# sprinkler_photon_0v2.net
KiCad netlist of a schematic drawn in Altium Designer
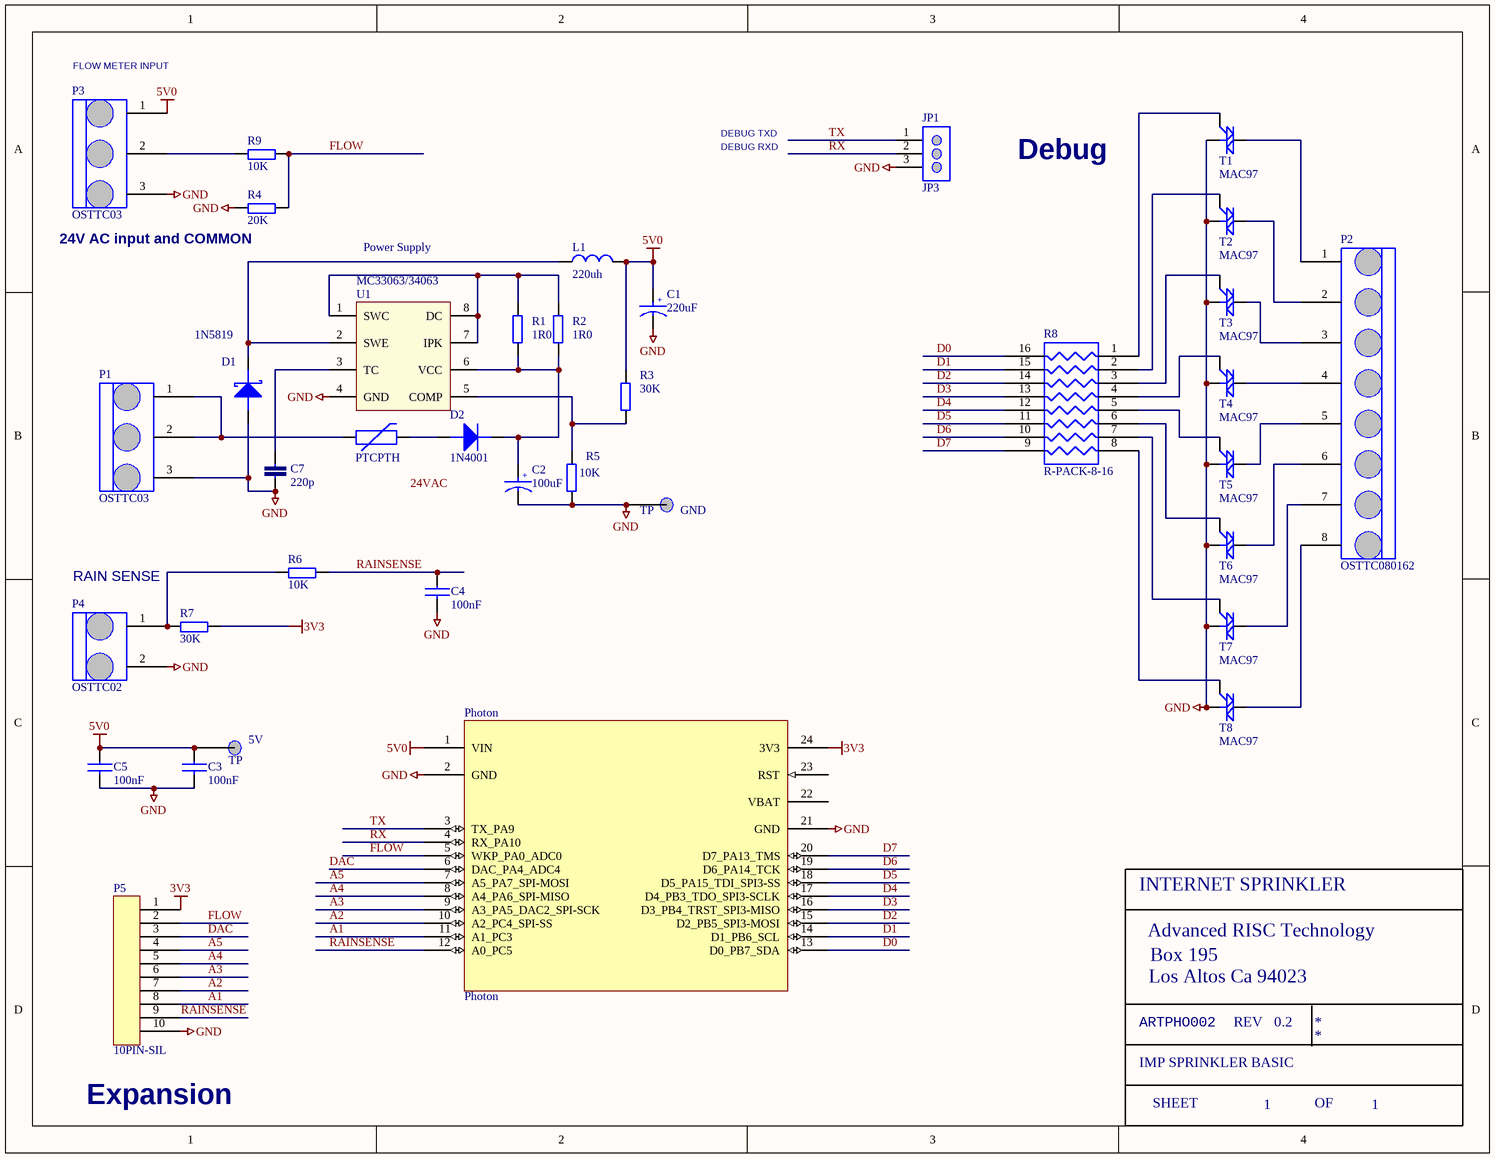
[diagram p0: sprinkler_photon_0v2.SchDoc]

(export (version "E")
  (design (tool "Eeschema 10.0.6"))
  (components
    (comp (ref "5V")
      (value "TP")
      (footprint "SIP-1")
      (description "Test Point")
      (libsource (lib "visible_energy") (part "TPS"))
    )
    (comp (ref "C1")
      (value "220uF")
      (footprint "RB-2MM-5MM")
      (description "CAP ALUM 220UF 6.3V 20% RADIAL")
      (fields (field (name "DISTRIBUTOR PART#") "493-1004-ND") (field (name "MANUFACTURER") "Nichicon"))
      (libsource (lib "visible_energy") (part "CAP POL"))
    )
    (comp (ref "C2")
      (value "100uF")
      (footprint "RB-3.5MM-8MM")
      (description "CAP ALUM 100UF 50V 20% RADIAL")
      (fields (field (name "DISTRIBUTOR PART#") "493-1107-ND") (field (name "MANUFACTURER") "Nichicon"))
      (libsource (lib "visible_energy") (part "CAP POL"))
    )
    (comp (ref "C3")
      (value "100nF")
      (footprint "RAD-0.1")
      (description "CAP CER 0.1UF 25V 10% RADIAL")
      (fields (field (name "DISTRIBUTOR PART#") "445-8421-ND") (field (name "MANUFACTURER") "TDK"))
      (libsource (lib "visible_energy") (part "CAP NP"))
    )
    (comp (ref "C4")
      (value "100nF")
      (footprint "RAD-0.1")
      (description "CAP CER 0.1UF 25V 10% RADIAL")
      (fields (field (name "DISTRIBUTOR PART#") "445-8421-ND") (field (name "MANUFACTURER") "TDK"))
      (libsource (lib "visible_energy") (part "CAP NP"))
    )
    (comp (ref "C5")
      (value "100nF")
      (footprint "RAD-0.1")
      (description "CAP CER 0.1UF 25V 10% RADIAL")
      (fields (field (name "DISTRIBUTOR PART#") "445-8421-ND") (field (name "MANUFACTURER") "TDK"))
      (libsource (lib "visible_energy") (part "CAP NP"))
    )
    (comp (ref "C7")
      (value "220p")
      (footprint "thruholepcb:RADCAP-0.1")
      (description "CAP CER 220PF 100V 5% RADIAL")
      (fields (field (name "DISTRIBUTOR PART#") "478-4847-ND") (field (name "MANUFACTURER") "AVX"))
      (libsource (lib "rcl") (part "C-EU025-024X044"))
    )
    (comp (ref "D1")
      (value "1N5819")
      (footprint "AXIAL-0.4 - DIODE")
      (description "DIODE SCHOTTKY 40V 1A DO-41")
      (fields (field (name "MANUFACTURER") "Diodes") (field (name "MANUFACTURER PART#") "1N5819-T"))
      (libsource (lib "visible_energy") (part "DIODE SCHOTTKY"))
    )
    (comp (ref "D2")
      (value "1N4001")
      (footprint "AXIAL-0.4 - DIODE")
      (description "RECTIFIER 50V 1A DO-41")
      (fields (field (name "MANUFACTURER") "Diodes") (field (name "MANUFACTURER PART#") "1N4001-T"))
      (libsource (lib "visible_energy") (part "DIODE"))
    )
    (comp (ref "GND")
      (value "TP")
      (footprint "SIP-1")
      (description "Test Point")
      (libsource (lib "visible_energy") (part "TPS"))
    )
    (comp (ref "JP1")
      (value "JP3")
      (footprint "SIP-3")
      (description "3 PIN JUMPER")
      (fields (field (name "MANUFACTURER") "Harwin") (field (name "DISTRIBUTOR PART#") "952-2264-ND"))
      (libsource (lib "connector") (part "JP3"))
    )
    (comp (ref "L1")
      (value "220uh")
      (footprint "thruholepcb:RB-5MM - 9MMDIA")
      (description "Inductor")
      (fields (field (name "MANUFACTURER") "Abracon") (field (name "DISTRIBUTOR PART#") "AIUR-02H-221K-ND"))
      (libsource (lib "visible_energy") (part "INDUCTOR"))
    )
    (comp (ref "P1")
      (value "OSTTC03")
      (footprint "OSTTC03")
      (description "TERMINAL BLOCK 5MM VERT 3POS PCB")
      (fields (field (name "MANUFACTURER") "Onshore") (field (name "DISTRIBUTOR PART#") "ED2601-ND"))
      (libsource (lib "connector") (part "3PIN-POW"))
    )
    (comp (ref "P2")
      (value "OSTTC080162")
      (footprint "OSTTC08")
      (description "TERMINAL BLOCK 5MM VERT 8POS PCB")
      (fields (field (name "MANUFACTURER") "OnShore") (field (name "DISTRIBUTOR PART#") "ED2606-ND"))
      (libsource (lib "connector") (part "8PIN-POW"))
    )
    (comp (ref "P3")
      (value "OSTTC03")
      (footprint "OSTTC03")
      (description "TERMINAL BLOCK 5MM VERT 3POS PCB")
      (fields (field (name "MANUFACTURER") "Onshore") (field (name "DISTRIBUTOR PART#") "ED2601-ND"))
      (libsource (lib "connector") (part "3PIN-POW"))
    )
    (comp (ref "P4")
      (value "OSTTC02")
      (footprint "OSTTC02")
      (description "TERMINAL BLOCK 5MM VERT 2POS PCB")
      (fields (field (name "MANUFACTURER") "Onshore") (field (name "DISTRIBUTOR PART#") "ED2600-ND"))
      (libsource (lib "connector") (part "2PIN-POW"))
    )
    (comp (ref "P5")
      (value "10PIN-SIL")
      (footprint "SIP-10")
      (fields
        (field (name "MANUFACTURER") "Harwin")
        (field (name "DISTRIBUTOR PART#") "952-1843-ND")
        (field (name "MANUFACTURER PART#") "M20-9991046")
      )
      (libsource (lib "connector") (part "10PIN-SIL"))
    )
    (comp (ref "Photon")
      (value "Photon")
      (footprint "PHOTON")
      (fields (field (name "DISTRIBUTOR PART#") "WRL-13764") (field (name "MANUFACTURER") "Particle.io"))
      (libsource (lib "visible_energy") (part "Photon"))
    )
    (comp (ref "PTC")
      (value "PTCPTH")
      (footprint "PTC")
      (description "FUSE PTC RESETTABLE .75A HOLD")
      (fields (field (name "DISTRIBUTOR PART#") "MF-R075-ND") (field (name "MANUFACTURER") "Bournes"))
      (libsource (lib "imp_sprinkler_0v1") (part "PTCPTH"))
    )
    (comp (ref "R1")
      (value "1R0")
      (footprint "AXIAL-0.5")
      (fields
        (field (name "DISTRIBUTOR PART#") "S1HCT-ND")
        (field (name "MANUFACTURER") "Stackpole")
        (field (name "MANUFACTURER PART#") "CFM12JT1R00")
      )
      (libsource (lib "rcl") (part "R-EU_0204/2V"))
    )
    (comp (ref "R2")
      (value "1R0")
      (footprint "AXIAL-0.5")
      (description "RES 1 OHM 1/2W 5% CF MINI")
      (fields (field (name "DISTRIBUTOR PART#") "S1HCT-ND") (field (name "MANUFACTURER") "Stackpole"))
      (libsource (lib "rcl") (part "R-EU_0204/2V"))
    )
    (comp (ref "R3")
      (value "30K")
      (footprint "AXIAL-0.4")
      (description "RES 30.1K OHM MET FILM .40W 1%")
      (fields (field (name "DISTRIBUTOR PART#") "PPC30.1KYCT-ND") (field (name "MANUFACTURER") "Vishay"))
      (libsource (lib "rcl") (part "R-EU_0204/7"))
    )
    (comp (ref "R4")
      (value "20K")
      (footprint "AXIAL-0.4")
      (description "RES 20K OHM 1/4W 5% CARBON FILM")
      (fields (field (name "DISTRIBUTOR PART#") "S10KQCT-ND") (field (name "MANUFACTURER") "Stackpole"))
      (libsource (lib "rcl") (part "R-EU_0204/7"))
    )
    (comp (ref "R5")
      (value "10K")
      (footprint "AXIAL-0.4")
      (description "RES MF 1/4W 10K OHM 1% AXIAL")
      (fields
        (field (name "DISTRIBUTOR PART#") "RNF14FTD10K0CT-ND")
        (field (name "MANUFACTURER") "Stackpole")
      )
      (libsource (lib "rcl") (part "R-EU_0204/7"))
    )
    (comp (ref "R6")
      (value "10K")
      (footprint "AXIAL-0.4")
      (description "RES 10K OHM 1/4W 5% CF MINI")
      (fields (field (name "DISTRIBUTOR PART#") "S10KQCT-ND") (field (name "MANUFACTURER") "Stackpole"))
      (libsource (lib "rcl") (part "R-EU_0204/7"))
    )
    (comp (ref "R7")
      (value "30K")
      (footprint "AXIAL-0.4")
      (description "RES 30.1K OHM MET FILM .40W 1%")
      (fields (field (name "DISTRIBUTOR PART#") "PPC30.1KYCT-ND") (field (name "MANUFACTURER") "Vishay"))
      (libsource (lib "rcl") (part "R-EU_0204/7"))
    )
    (comp (ref "R8")
      (value "R-PACK-8-16")
      (footprint "DIP-16")
      (description "RES ARRAY 330 OHM 8 RES 16-DIP")
      (fields (field (name "MANUFACTURER") "Bournes") (field (name "DISTRIBUTOR PART#") "4116R-1-331LF-ND"))
      (libsource (lib "descrete") (part "R-PACK-8-16"))
    )
    (comp (ref "R9")
      (value "10K")
      (footprint "AXIAL-0.4")
      (description "RES 10K OHM 1/4W 5% CF MINI")
      (fields (field (name "DISTRIBUTOR PART#") "S10KQCT-ND") (field (name "MANUFACTURER") "Stackpole"))
      (libsource (lib "rcl") (part "R-EU_0204/7"))
    )
    (comp (ref "T1")
      (value "MAC97")
      (footprint "imp_sprinkler_0v1:TO-92")
      (description "THYRISTOR TRIAC .6A 600V TO92")
      (fields (field (name "DISTRIBUTOR PART#") "MAC97A8GOS-ND") (field (name "MANUFACTURER") "ON"))
      (libsource (lib "SparkFun") (part "LX807DE"))
    )
    (comp (ref "T2")
      (value "MAC97")
      (footprint "imp_sprinkler_0v1:TO-92")
      (description "THYRISTOR TRIAC .6A 600V TO92")
      (fields (field (name "DISTRIBUTOR PART#") "MAC97A8GOS-ND") (field (name "MANUFACTURER") "ON"))
      (libsource (lib "SparkFun") (part "LX807DE"))
    )
    (comp (ref "T3")
      (value "MAC97")
      (footprint "TO-92")
      (description "THYRISTOR TRIAC .6A 600V TO92")
      (fields (field (name "DISTRIBUTOR PART#") "MAC97A8GOS-ND") (field (name "MANUFACTURER") "ON"))
      (libsource (lib "SparkFun") (part "LX807DE"))
    )
    (comp (ref "T4")
      (value "MAC97")
      (footprint "TO-92")
      (description "THYRISTOR TRIAC .6A 600V TO92")
      (fields (field (name "DISTRIBUTOR PART#") "MAC97A8GOS-ND") (field (name "MANUFACTURER") "ON"))
      (libsource (lib "SparkFun") (part "LX807DE"))
    )
    (comp (ref "T5")
      (value "MAC97")
      (footprint "TO-92")
      (description "THYRISTOR TRIAC .6A 600V TO92")
      (fields (field (name "DISTRIBUTOR PART#") "MAC97A8GOS-ND") (field (name "MANUFACTURER") "ON"))
      (libsource (lib "SparkFun") (part "LX807DE"))
    )
    (comp (ref "T6")
      (value "MAC97")
      (footprint "TO-92")
      (description "THYRISTOR TRIAC .6A 600V TO92")
      (fields (field (name "DISTRIBUTOR PART#") "MAC97A8GOS-ND") (field (name "MANUFACTURER") "ON"))
      (libsource (lib "SparkFun") (part "LX807DE"))
    )
    (comp (ref "T7")
      (value "MAC97")
      (footprint "TO-92")
      (description "THYRISTOR TRIAC .6A 600V TO92")
      (fields (field (name "DISTRIBUTOR PART#") "MAC97A8GOS-ND") (field (name "MANUFACTURER") "ON"))
      (libsource (lib "SparkFun") (part "LX807DE"))
    )
    (comp (ref "T8")
      (value "MAC97")
      (footprint "TO-92")
      (description "THYRISTOR TRIAC .6A 600V TO92")
      (fields (field (name "DISTRIBUTOR PART#") "MAC97A8GOS-ND") (field (name "MANUFACTURER") "ON"))
      (libsource (lib "SparkFun") (part "LX807DE"))
    )
    (comp (ref "U1")
      (value "MC33063/34063")
      (footprint "DIP8")
      (fields
        (field (name "DISTRIBUTOR PART#") "296-17764-5-ND")
        (field (name "MANUFACTURER") "TI")
        (field (name "MANUFACTURER PART#") "MC33063AP")
      )
      (libsource (lib "IC") (part "MC33063/MC34063P"))
    )
  )
  (nets
    (net (code "2") (name "/A1") (class "Default")
      (node (ref "P5") (pin "8") (pintype "passive"))
      (node (ref "Photon") (pin "11") (pinfunction "A1_PC3_11") (pintype "bidirectional"))
    )
    (net (code "3") (name "/A2") (class "Default")
      (node (ref "P5") (pin "7") (pintype "passive"))
      (node (ref "Photon") (pin "10") (pinfunction "A2_PC4_SPI-SS_10") (pintype "bidirectional"))
    )
    (net (code "4") (name "/A3") (class "Default")
      (node (ref "P5") (pin "6") (pintype "passive"))
      (node (ref "Photon") (pin "9") (pinfunction "A3_PA5_DAC2_SPI-SCK_9") (pintype "bidirectional"))
    )
    (net (code "5") (name "/A4") (class "Default")
      (node (ref "P5") (pin "5") (pintype "passive"))
      (node (ref "Photon") (pin "8") (pinfunction "A4_PA6_SPI-MISO_8") (pintype "bidirectional"))
    )
    (net (code "6") (name "/A5") (class "Default")
      (node (ref "P5") (pin "4") (pintype "passive"))
      (node (ref "Photon") (pin "7") (pinfunction "A5_PA7_SPI-MOSI_7") (pintype "bidirectional"))
    )
    (net (code "7") (name "/D0") (class "Default")
      (node (ref "Photon") (pin "13") (pinfunction "D0_PB7_SDA_13") (pintype "bidirectional"))
      (node (ref "R8") (pin "16") (pinfunction "R1_16") (pintype "passive"))
    )
    (net (code "8") (name "/D1") (class "Default")
      (node (ref "Photon") (pin "14") (pinfunction "D1_PB6_SCL_14") (pintype "bidirectional"))
      (node (ref "R8") (pin "15") (pinfunction "R2_15") (pintype "passive"))
    )
    (net (code "9") (name "/D2") (class "Default")
      (node (ref "Photon") (pin "15") (pinfunction "D2_PB5_SPI3-MOSI_15") (pintype "bidirectional"))
      (node (ref "R8") (pin "14") (pinfunction "R3_14") (pintype "passive"))
    )
    (net (code "10") (name "/D3") (class "Default")
      (node (ref "Photon") (pin "16") (pinfunction "D3_PB4_TRST_SPI3-MISO_16") (pintype "bidirectional"))
      (node (ref "R8") (pin "13") (pinfunction "R4_13") (pintype "passive"))
    )
    (net (code "11") (name "/D4") (class "Default")
      (node (ref "Photon") (pin "17") (pinfunction "D4_PB3_TDO_SPI3-SCLK_17") (pintype "bidirectional"))
      (node (ref "R8") (pin "12") (pinfunction "R5_12") (pintype "passive"))
    )
    (net (code "12") (name "/D5") (class "Default")
      (node (ref "Photon") (pin "18") (pinfunction "D5_PA15_TDI_SPI3-SS_18") (pintype "bidirectional"))
      (node (ref "R8") (pin "11") (pinfunction "R6_11") (pintype "passive"))
    )
    (net (code "13") (name "/D6") (class "Default")
      (node (ref "Photon") (pin "19") (pinfunction "D6_PA14_TCK_19") (pintype "bidirectional"))
      (node (ref "R8") (pin "10") (pinfunction "R7_10") (pintype "passive"))
    )
    (net (code "14") (name "/D7") (class "Default")
      (node (ref "Photon") (pin "20") (pinfunction "D7_PA13_TMS_20") (pintype "bidirectional"))
      (node (ref "R8") (pin "9") (pinfunction "R8_9") (pintype "passive"))
    )
    (net (code "15") (name "/DAC") (class "Default")
      (node (ref "P5") (pin "3") (pintype "passive"))
      (node (ref "Photon") (pin "6") (pinfunction "DAC_PA4_ADC4_6") (pintype "bidirectional"))
    )
    (net (code "16") (name "/FLOW") (class "Default")
      (node (ref "P5") (pin "2") (pintype "passive"))
      (node (ref "Photon") (pin "5") (pinfunction "WKP_PA0_ADC0_5") (pintype "bidirectional"))
      (node (ref "R4") (pin "2") (pinfunction "2_2") (pintype "passive"))
      (node (ref "R9") (pin "2") (pinfunction "2_2") (pintype "passive"))
    )
    (net (code "17") (name "/RAINSENSE") (class "Default")
      (node (ref "C4") (pin "1") (pinfunction "1_1") (pintype "passive"))
      (node (ref "P5") (pin "9") (pintype "passive"))
      (node (ref "Photon") (pin "12") (pinfunction "A0_PC5_12") (pintype "bidirectional"))
      (node (ref "R6") (pin "2") (pinfunction "2_2") (pintype "passive"))
    )
    (net (code "18") (name "/RX") (class "Default")
      (node (ref "JP1") (pin "2") (pinfunction "2_2") (pintype "passive"))
      (node (ref "Photon") (pin "4") (pinfunction "RX_PA10_4") (pintype "bidirectional"))
    )
    (net (code "19") (name "/TX") (class "Default")
      (node (ref "JP1") (pin "1") (pinfunction "1_1") (pintype "passive"))
      (node (ref "Photon") (pin "3") (pinfunction "TX_PA9_3") (pintype "bidirectional"))
    )
    (net (code "20") (name "3V3") (class "Default")
      (node (ref "P5") (pin "1") (pintype "passive"))
      (node (ref "Photon") (pin "24") (pinfunction "3V3_24") (pintype "power_in"))
      (node (ref "R7") (pin "2") (pinfunction "2_2") (pintype "passive"))
    )
    (net (code "21") (name "5V0") (class "Default")
      (node (ref "5V") (pin "1") (pinfunction "1_1") (pintype "passive"))
      (node (ref "C1") (pin "1") (pinfunction "1_1") (pintype "passive"))
      (node (ref "C3") (pin "1") (pinfunction "1_1") (pintype "passive"))
      (node (ref "C5") (pin "1") (pinfunction "1_1") (pintype "passive"))
      (node (ref "L1") (pin "2") (pinfunction "2_2") (pintype "passive"))
      (node (ref "P3") (pin "1") (pintype "passive"))
      (node (ref "Photon") (pin "1") (pinfunction "VIN_1") (pintype "power_in"))
      (node (ref "R3") (pin "1") (pinfunction "1_1") (pintype "passive"))
    )
    (net (code "22") (name "GND") (class "Default")
      (node (ref "C1") (pin "2") (pinfunction "2_2") (pintype "passive"))
      (node (ref "C2") (pin "2") (pinfunction "2_2") (pintype "passive"))
      (node (ref "C3") (pin "2") (pinfunction "2_2") (pintype "passive"))
      (node (ref "C4") (pin "2") (pinfunction "2_2") (pintype "passive"))
      (node (ref "C5") (pin "2") (pinfunction "2_2") (pintype "passive"))
      (node (ref "C7") (pin "2") (pinfunction "2_2") (pintype "passive"))
      (node (ref "D1") (pin "1") (pinfunction "A_1") (pintype "passive"))
      (node (ref "GND") (pin "1") (pinfunction "1_1") (pintype "passive"))
      (node (ref "JP1") (pin "3") (pinfunction "3_3") (pintype "passive"))
      (node (ref "P1") (pin "3") (pintype "passive"))
      (node (ref "P3") (pin "3") (pintype "passive"))
      (node (ref "P4") (pin "2") (pintype "passive"))
      (node (ref "P5") (pin "10") (pintype "passive"))
      (node (ref "Photon") (pin "2") (pinfunction "GND_2") (pintype "power_in"))
      (node (ref "Photon") (pin "21") (pinfunction "GND_21") (pintype "power_in"))
      (node (ref "R4") (pin "1") (pinfunction "1_1") (pintype "passive"))
      (node (ref "R5") (pin "2") (pinfunction "2_2") (pintype "passive"))
      (node (ref "T1") (pin "1") (pinfunction "M1_1") (pintype "passive"))
      (node (ref "T2") (pin "1") (pinfunction "M1_1") (pintype "passive"))
      (node (ref "T3") (pin "1") (pinfunction "M1_1") (pintype "passive"))
      (node (ref "T4") (pin "1") (pinfunction "M1_1") (pintype "passive"))
      (node (ref "T5") (pin "1") (pinfunction "M1_1") (pintype "passive"))
      (node (ref "T6") (pin "1") (pinfunction "M1_1") (pintype "passive"))
      (node (ref "T7") (pin "1") (pinfunction "M1_1") (pintype "passive"))
      (node (ref "T8") (pin "1") (pinfunction "M1_1") (pintype "passive"))
      (node (ref "U1") (pin "4") (pinfunction "GND_4") (pintype "passive"))
    )
    (net (code "23") (name "Net-(D1-K)") (class "Default")
      (node (ref "D1") (pin "2") (pinfunction "K_2") (pintype "passive"))
      (node (ref "L1") (pin "1") (pinfunction "1_1") (pintype "passive"))
      (node (ref "U1") (pin "2") (pinfunction "SWE_2") (pintype "passive"))
    )
    (net (code "24") (name "Net-(D2-A)") (class "Default")
      (node (ref "D2") (pin "1") (pinfunction "A_1") (pintype "passive"))
      (node (ref "PTC") (pin "2") (pinfunction "2_2") (pintype "passive"))
    )
    (net (code "25") (name "Net-(D2-K)") (class "Default")
      (node (ref "C2") (pin "1") (pinfunction "1_1") (pintype "passive"))
      (node (ref "D2") (pin "2") (pinfunction "K_2") (pintype "passive"))
      (node (ref "R1") (pin "2") (pinfunction "2_2") (pintype "passive"))
      (node (ref "R2") (pin "2") (pinfunction "2_2") (pintype "passive"))
      (node (ref "U1") (pin "6") (pinfunction "VCC_6") (pintype "passive"))
    )
    (net (code "26") (name "Net-(P1-Pad1)") (class "Default")
      (node (ref "P1") (pin "1") (pintype "passive"))
      (node (ref "P1") (pin "2") (pintype "passive"))
      (node (ref "PTC") (pin "1") (pinfunction "1_1") (pintype "passive"))
    )
    (net (code "27") (name "Net-(P3-Pad2)") (class "Default")
      (node (ref "P3") (pin "2") (pintype "passive"))
      (node (ref "R9") (pin "1") (pinfunction "1_1") (pintype "passive"))
    )
    (net (code "28") (name "Net-(P4-Pad1)") (class "Default")
      (node (ref "P4") (pin "1") (pintype "passive"))
      (node (ref "R6") (pin "1") (pinfunction "1_1") (pintype "passive"))
      (node (ref "R7") (pin "1") (pinfunction "1_1") (pintype "passive"))
    )
    (net (code "29") (name "Net-(T1-G)") (class "Default")
      (node (ref "R8") (pin "1") (pinfunction "R1_1") (pintype "passive"))
      (node (ref "T1") (pin "2") (pinfunction "G_2") (pintype "passive"))
    )
    (net (code "30") (name "Net-(T1-M2)") (class "Default")
      (node (ref "P2") (pin "1") (pintype "passive"))
      (node (ref "T1") (pin "3") (pinfunction "M2_3") (pintype "passive"))
    )
    (net (code "31") (name "Net-(T2-G)") (class "Default")
      (node (ref "R8") (pin "2") (pinfunction "R2_2") (pintype "passive"))
      (node (ref "T2") (pin "2") (pinfunction "G_2") (pintype "passive"))
    )
    (net (code "32") (name "Net-(T2-M2)") (class "Default")
      (node (ref "P2") (pin "2") (pintype "passive"))
      (node (ref "T2") (pin "3") (pinfunction "M2_3") (pintype "passive"))
    )
    (net (code "33") (name "Net-(T3-G)") (class "Default")
      (node (ref "R8") (pin "3") (pinfunction "R3_3") (pintype "passive"))
      (node (ref "T3") (pin "2") (pinfunction "G_2") (pintype "passive"))
    )
    (net (code "34") (name "Net-(T3-M2)") (class "Default")
      (node (ref "P2") (pin "3") (pintype "passive"))
      (node (ref "T3") (pin "3") (pinfunction "M2_3") (pintype "passive"))
    )
    (net (code "35") (name "Net-(T4-G)") (class "Default")
      (node (ref "R8") (pin "4") (pinfunction "R4_4") (pintype "passive"))
      (node (ref "T4") (pin "2") (pinfunction "G_2") (pintype "passive"))
    )
    (net (code "36") (name "Net-(T4-M2)") (class "Default")
      (node (ref "P2") (pin "4") (pintype "passive"))
      (node (ref "T4") (pin "3") (pinfunction "M2_3") (pintype "passive"))
    )
    (net (code "37") (name "Net-(T5-G)") (class "Default")
      (node (ref "R8") (pin "5") (pinfunction "R5_5") (pintype "passive"))
      (node (ref "T5") (pin "2") (pinfunction "G_2") (pintype "passive"))
    )
    (net (code "38") (name "Net-(T5-M2)") (class "Default")
      (node (ref "P2") (pin "5") (pintype "passive"))
      (node (ref "T5") (pin "3") (pinfunction "M2_3") (pintype "passive"))
    )
    (net (code "39") (name "Net-(T6-G)") (class "Default")
      (node (ref "R8") (pin "6") (pinfunction "R6_6") (pintype "passive"))
      (node (ref "T6") (pin "2") (pinfunction "G_2") (pintype "passive"))
    )
    (net (code "40") (name "Net-(T6-M2)") (class "Default")
      (node (ref "P2") (pin "6") (pintype "passive"))
      (node (ref "T6") (pin "3") (pinfunction "M2_3") (pintype "passive"))
    )
    (net (code "41") (name "Net-(T7-G)") (class "Default")
      (node (ref "R8") (pin "7") (pinfunction "R7_7") (pintype "passive"))
      (node (ref "T7") (pin "2") (pinfunction "G_2") (pintype "passive"))
    )
    (net (code "42") (name "Net-(T7-M2)") (class "Default")
      (node (ref "P2") (pin "7") (pintype "passive"))
      (node (ref "T7") (pin "3") (pinfunction "M2_3") (pintype "passive"))
    )
    (net (code "43") (name "Net-(T8-G)") (class "Default")
      (node (ref "R8") (pin "8") (pinfunction "R8_8") (pintype "passive"))
      (node (ref "T8") (pin "2") (pinfunction "G_2") (pintype "passive"))
    )
    (net (code "44") (name "Net-(T8-M2)") (class "Default")
      (node (ref "P2") (pin "8") (pintype "passive"))
      (node (ref "T8") (pin "3") (pinfunction "M2_3") (pintype "passive"))
    )
    (net (code "45") (name "Net-(U1-COMP)") (class "Default")
      (node (ref "R3") (pin "2") (pinfunction "2_2") (pintype "passive"))
      (node (ref "R5") (pin "1") (pinfunction "1_1") (pintype "passive"))
      (node (ref "U1") (pin "5") (pinfunction "COMP_5") (pintype "passive"))
    )
    (net (code "46") (name "Net-(U1-DC)") (class "Default")
      (node (ref "R1") (pin "1") (pinfunction "1_1") (pintype "passive"))
      (node (ref "R2") (pin "1") (pinfunction "1_1") (pintype "passive"))
      (node (ref "U1") (pin "1") (pinfunction "SWC_1") (pintype "passive"))
      (node (ref "U1") (pin "7") (pinfunction "IPK_7") (pintype "passive"))
      (node (ref "U1") (pin "8") (pinfunction "DC_8") (pintype "passive"))
    )
    (net (code "47") (name "Net-(U1-TC)") (class "Default")
      (node (ref "C7") (pin "1") (pinfunction "1_1") (pintype "passive"))
      (node (ref "U1") (pin "3") (pinfunction "TC_3") (pintype "passive"))
    )
    (net (code "48") (name "unconnected-(Photon-RST-Pad23)") (class "Default")
      (node (ref "Photon") (pin "23") (pinfunction "RST_23") (pintype "input"))
    )
    (net (code "49") (name "unconnected-(Photon-VBAT-Pad22)") (class "Default")
      (node (ref "Photon") (pin "22") (pinfunction "VBAT_22") (pintype "power_in"))
    )
  )
)
